# MainBoard.net
KiCad netlist of a schematic drawn in EAGLE
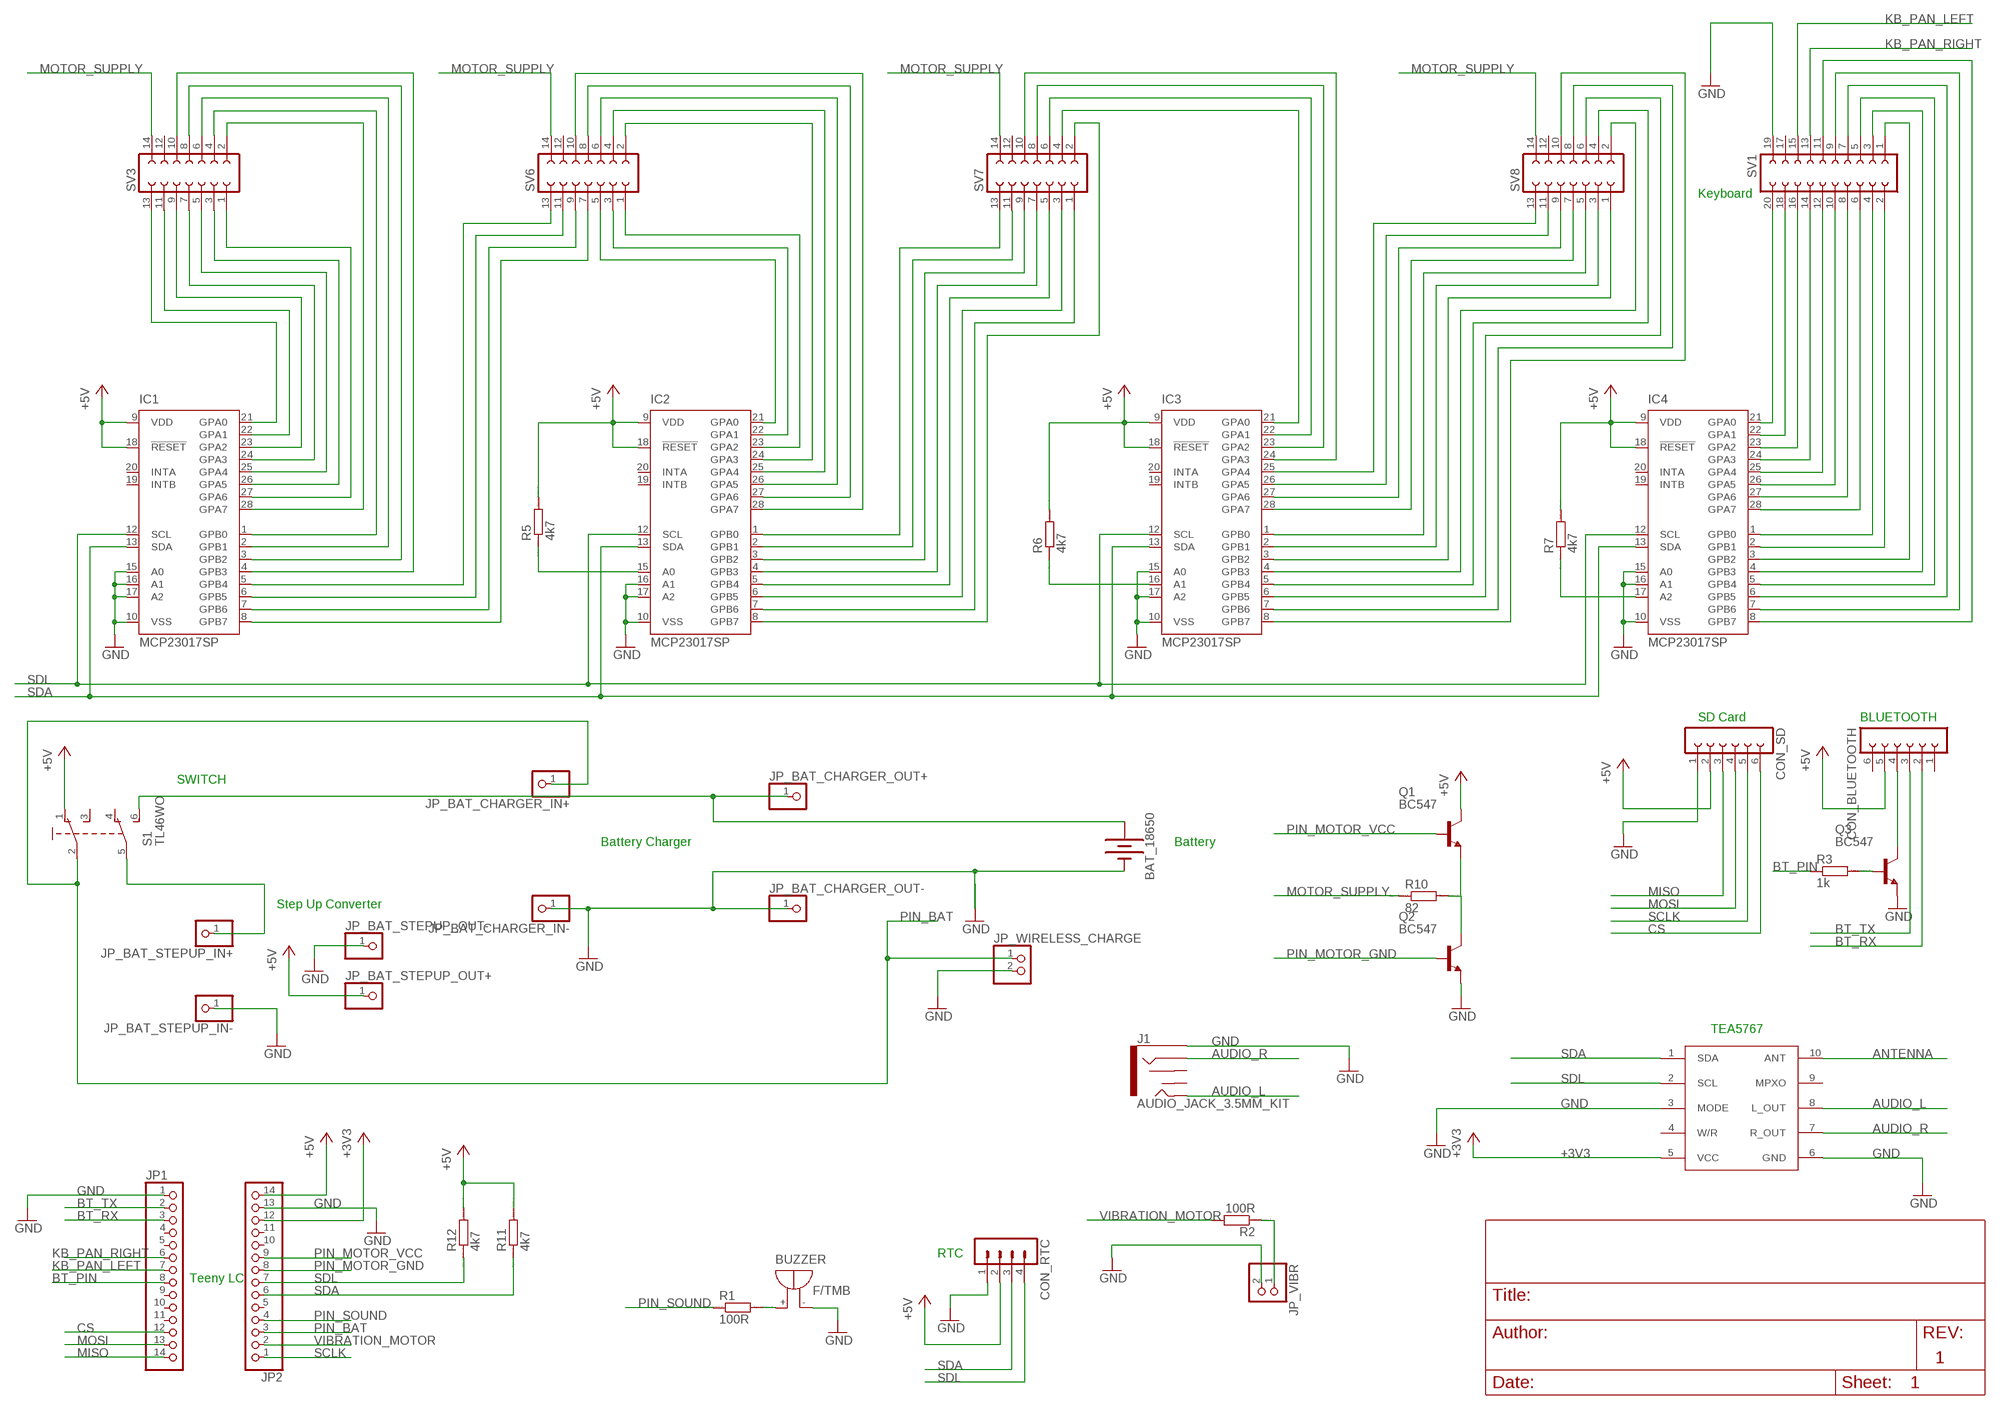
[diagram p0: schematic, sheet 1]

(export (version "E")
  (design (tool "Eeschema 10.0.6"))
  (components
    (comp (ref "BAT_18650")
      (value "BATTERY-18650")
      (footprint "eagle-import:BATTERY_18650-HOLDER")
      (libsource (lib "eagle-import") (part "BATTERY-18650"))
    )
    (comp (ref "BUZZER")
      (value "F/TMB")
      (footprint "eagle-import:F_TMB")
      (libsource (lib "eagle-import") (part "F/TMB"))
    )
    (comp (ref "CON_BLUETOOTH")
      (value "FE06-1")
      (footprint "eagle-import:FE06")
      (libsource (lib "eagle-import") (part "FE06-1"))
    )
    (comp (ref "CON_RTC")
      (value "MA04-1")
      (footprint "eagle-import:MA04-1")
      (libsource (lib "eagle-import") (part "MA04-1"))
    )
    (comp (ref "CON_SD")
      (value "FE06-1")
      (footprint "eagle-import:FE06")
      (libsource (lib "eagle-import") (part "FE06-1"))
    )
    (comp (ref "IC1")
      (value "MCP23017SP")
      (footprint "eagle-import:DIL28-3")
      (fields (field (name "MF") "MICROCHIP") (field (name "MPN") "MCP23017-E/SP"))
      (libsource (lib "eagle-import") (part "MCP23017SP"))
    )
    (comp (ref "IC2")
      (value "MCP23017SP")
      (footprint "eagle-import:DIL28-3")
      (fields (field (name "MF") "MICROCHIP") (field (name "MPN") "MCP23017-E/SP"))
      (libsource (lib "eagle-import") (part "MCP23017SP"))
    )
    (comp (ref "IC3")
      (value "MCP23017SP")
      (footprint "eagle-import:DIL28-3")
      (fields (field (name "MF") "MICROCHIP") (field (name "MPN") "MCP23017-E/SP"))
      (libsource (lib "eagle-import") (part "MCP23017SP"))
    )
    (comp (ref "IC4")
      (value "MCP23017SP")
      (footprint "eagle-import:DIL28-3")
      (fields (field (name "MF") "MICROCHIP") (field (name "MPN") "MCP23017-E/SP"))
      (libsource (lib "eagle-import") (part "MCP23017SP"))
    )
    (comp (ref "J1")
      (value "AUDIO_JACK_3.5MM_KIT")
      (footprint "eagle-import:AUDIO-JACK-KIT")
      (libsource (lib "eagle-import") (part "AUDIO_JACK_3.5MM_KIT"))
    )
    (comp (ref "JP1")
      (value "PINHD-1X14")
      (footprint "eagle-import:1X14")
      (libsource (lib "eagle-import") (part "PINHD-1X14"))
    )
    (comp (ref "JP2")
      (value "PINHD-1X14")
      (footprint "eagle-import:1X14")
      (libsource (lib "eagle-import") (part "PINHD-1X14"))
    )
    (comp (ref "JP_BAT_CHARGER_IN+")
      (value "PINHD-1X1")
      (footprint "eagle-import:1X01")
      (libsource (lib "eagle-import") (part "PINHD-1X1"))
    )
    (comp (ref "JP_BAT_CHARGER_IN-")
      (value "PINHD-1X1")
      (footprint "eagle-import:1X01")
      (libsource (lib "eagle-import") (part "PINHD-1X1"))
    )
    (comp (ref "JP_BAT_CHARGER_OUT+")
      (value "PINHD-1X1")
      (footprint "eagle-import:1X01")
      (libsource (lib "eagle-import") (part "PINHD-1X1"))
    )
    (comp (ref "JP_BAT_CHARGER_OUT-")
      (value "PINHD-1X1")
      (footprint "eagle-import:1X01")
      (libsource (lib "eagle-import") (part "PINHD-1X1"))
    )
    (comp (ref "JP_BAT_STEPUP_IN+")
      (value "PINHD-1X1")
      (footprint "eagle-import:1X01")
      (libsource (lib "eagle-import") (part "PINHD-1X1"))
    )
    (comp (ref "JP_BAT_STEPUP_IN-")
      (value "PINHD-1X1")
      (footprint "eagle-import:1X01")
      (libsource (lib "eagle-import") (part "PINHD-1X1"))
    )
    (comp (ref "JP_BAT_STEPUP_OUT+")
      (value "PINHD-1X1")
      (footprint "eagle-import:1X01")
      (libsource (lib "eagle-import") (part "PINHD-1X1"))
    )
    (comp (ref "JP_BAT_STEPUP_OUT-")
      (value "PINHD-1X1")
      (footprint "eagle-import:1X01")
      (libsource (lib "eagle-import") (part "PINHD-1X1"))
    )
    (comp (ref "JP_VIBR")
      (value "PINHD-1X2")
      (footprint "eagle-import:1X02")
      (libsource (lib "eagle-import") (part "PINHD-1X2"))
    )
    (comp (ref "JP_WIRELESS_CHARGE")
      (value "PINHD-1X2")
      (footprint "eagle-import:1X02")
      (libsource (lib "eagle-import") (part "PINHD-1X2"))
    )
    (comp (ref "Q1")
      (value "BC547")
      (footprint "eagle-import:TO92")
      (libsource (lib "eagle-import") (part "BC547"))
    )
    (comp (ref "Q2")
      (value "BC547")
      (footprint "eagle-import:TO92")
      (libsource (lib "eagle-import") (part "BC547"))
    )
    (comp (ref "Q3")
      (value "BC547")
      (footprint "eagle-import:TO92")
      (libsource (lib "eagle-import") (part "BC547"))
    )
    (comp (ref "R1")
      (value "100R")
      (footprint "eagle-import:R1206")
      (libsource (lib "eagle-import") (part "RR1206"))
    )
    (comp (ref "R2")
      (value "100R")
      (footprint "eagle-import:R1206")
      (libsource (lib "eagle-import") (part "RR1206"))
    )
    (comp (ref "R3")
      (value "1k")
      (footprint "eagle-import:R1206")
      (libsource (lib "eagle-import") (part "RR1206"))
    )
    (comp (ref "R5")
      (value "4k7")
      (footprint "eagle-import:R1206")
      (libsource (lib "eagle-import") (part "RR1206"))
    )
    (comp (ref "R6")
      (value "4k7")
      (footprint "eagle-import:R1206")
      (libsource (lib "eagle-import") (part "RR1206"))
    )
    (comp (ref "R7")
      (value "4k7")
      (footprint "eagle-import:R1206")
      (libsource (lib "eagle-import") (part "RR1206"))
    )
    (comp (ref "R10")
      (value "82")
      (footprint "eagle-import:R1206")
      (libsource (lib "eagle-import") (part "RR1206"))
    )
    (comp (ref "R11")
      (value "4k7")
      (footprint "eagle-import:R1206")
      (libsource (lib "eagle-import") (part "RR1206"))
    )
    (comp (ref "R12")
      (value "4k7")
      (footprint "eagle-import:R1206")
      (libsource (lib "eagle-import") (part "RR1206"))
    )
    (comp (ref "S1")
      (value "TL46WO")
      (footprint "eagle-import:TL4XWO")
      (libsource (lib "eagle-import") (part "TL46WO"))
    )
    (comp (ref "SV1")
      (value "FE10-2")
      (footprint "eagle-import:FE10-2")
      (libsource (lib "eagle-import") (part "FE10-2"))
    )
    (comp (ref "SV3")
      (value "FE07-2")
      (footprint "eagle-import:FE07-2")
      (libsource (lib "eagle-import") (part "FE07-2"))
    )
    (comp (ref "SV6")
      (value "FE07-2")
      (footprint "eagle-import:FE07-2")
      (libsource (lib "eagle-import") (part "FE07-2"))
    )
    (comp (ref "SV7")
      (value "FE07-2")
      (footprint "eagle-import:FE07-2")
      (libsource (lib "eagle-import") (part "FE07-2"))
    )
    (comp (ref "SV8")
      (value "FE07-2")
      (footprint "eagle-import:FE07-2")
      (libsource (lib "eagle-import") (part "FE07-2"))
    )
    (comp (ref "TEA5767")
      (value "TEA5767BREAKOUT")
      (footprint "eagle-import:TEA5767MM2")
      (libsource (lib "eagle-import") (part "TEA5767BREAKOUT"))
    )
  )
  (nets
    (net (code "1") (name "+3V3") (class "Default")
      (node (ref "JP2") (pin "12") (pinfunction "12_12") (pintype "passive"))
      (node (ref "TEA5767") (pin "5") (pinfunction "VCC_5") (pintype "bidirectional"))
    )
    (net (code "2") (name "+5V") (class "Default")
      (node (ref "CON_BLUETOOTH") (pin "5") (pinfunction "5_5") (pintype "passive"))
      (node (ref "CON_RTC") (pin "2") (pinfunction "2_2") (pintype "passive"))
      (node (ref "CON_SD") (pin "2") (pinfunction "2_2") (pintype "passive"))
      (node (ref "IC1") (pin "18") (pinfunction "~{RESET}_18") (pintype "input"))
      (node (ref "IC1") (pin "9") (pinfunction "VDD_9") (pintype "power_in"))
      (node (ref "IC2") (pin "18") (pinfunction "~{RESET}_18") (pintype "input"))
      (node (ref "IC2") (pin "9") (pinfunction "VDD_9") (pintype "power_in"))
      (node (ref "IC3") (pin "18") (pinfunction "~{RESET}_18") (pintype "input"))
      (node (ref "IC3") (pin "9") (pinfunction "VDD_9") (pintype "power_in"))
      (node (ref "IC4") (pin "18") (pinfunction "~{RESET}_18") (pintype "input"))
      (node (ref "IC4") (pin "9") (pinfunction "VDD_9") (pintype "power_in"))
      (node (ref "JP2") (pin "14") (pinfunction "14_14") (pintype "passive"))
      (node (ref "JP_BAT_STEPUP_OUT+") (pin "1") (pinfunction "1_1") (pintype "passive"))
      (node (ref "Q1") (pin "3") (pinfunction "C_3") (pintype "passive"))
      (node (ref "R11") (pin "2") (pinfunction "2_2") (pintype "passive"))
      (node (ref "R12") (pin "2") (pinfunction "2_2") (pintype "passive"))
      (node (ref "R5") (pin "2") (pinfunction "2_2") (pintype "passive"))
      (node (ref "R6") (pin "2") (pinfunction "2_2") (pintype "passive"))
      (node (ref "R7") (pin "2") (pinfunction "2_2") (pintype "passive"))
      (node (ref "S1") (pin "1") (pinfunction "O_1") (pintype "passive"))
    )
    (net (code "3") (name "/ANTENNA") (class "Default")
      (node (ref "TEA5767") (pin "10") (pinfunction "ANT_10") (pintype "bidirectional"))
    )
    (net (code "4") (name "/AUDIO_L") (class "Default")
      (node (ref "J1") (pin "TIP") (pinfunction "TIP_TIP") (pintype "bidirectional"))
      (node (ref "TEA5767") (pin "8") (pinfunction "L_OUT_8") (pintype "bidirectional"))
    )
    (net (code "5") (name "/AUDIO_R") (class "Default")
      (node (ref "J1") (pin "RING") (pinfunction "RING_RING") (pintype "bidirectional"))
      (node (ref "TEA5767") (pin "7") (pinfunction "R_OUT_7") (pintype "bidirectional"))
    )
    (net (code "6") (name "/BT_PIN") (class "Default")
      (node (ref "JP1") (pin "8") (pinfunction "8_8") (pintype "passive"))
      (node (ref "R3") (pin "1") (pinfunction "1_1") (pintype "passive"))
    )
    (net (code "7") (name "/BT_RX") (class "Default")
      (node (ref "CON_BLUETOOTH") (pin "2") (pinfunction "2_2") (pintype "passive"))
      (node (ref "JP1") (pin "3") (pinfunction "3_3") (pintype "passive"))
    )
    (net (code "8") (name "/BT_TX") (class "Default")
      (node (ref "CON_BLUETOOTH") (pin "3") (pinfunction "3_3") (pintype "passive"))
      (node (ref "JP1") (pin "2") (pinfunction "2_2") (pintype "passive"))
    )
    (net (code "9") (name "/CS") (class "Default")
      (node (ref "CON_SD") (pin "6") (pinfunction "6_6") (pintype "passive"))
      (node (ref "JP1") (pin "12") (pinfunction "12_12") (pintype "passive"))
    )
    (net (code "10") (name "/KB_PAN_LEFT") (class "Default")
      (node (ref "JP1") (pin "7") (pinfunction "7_7") (pintype "passive"))
      (node (ref "SV1") (pin "15") (pinfunction "15_15") (pintype "passive"))
    )
    (net (code "11") (name "/KB_PAN_RIGHT") (class "Default")
      (node (ref "JP1") (pin "6") (pinfunction "6_6") (pintype "passive"))
      (node (ref "SV1") (pin "13") (pinfunction "13_13") (pintype "passive"))
    )
    (net (code "12") (name "/MISO") (class "Default")
      (node (ref "CON_SD") (pin "3") (pinfunction "3_3") (pintype "passive"))
      (node (ref "JP1") (pin "14") (pinfunction "14_14") (pintype "passive"))
    )
    (net (code "13") (name "/MOSI") (class "Default")
      (node (ref "CON_SD") (pin "4") (pinfunction "4_4") (pintype "passive"))
      (node (ref "JP1") (pin "13") (pinfunction "13_13") (pintype "passive"))
    )
    (net (code "14") (name "/MOTOR_SUPPLY") (class "Default")
      (node (ref "R10") (pin "1") (pinfunction "1_1") (pintype "passive"))
      (node (ref "SV3") (pin "14") (pinfunction "14_14") (pintype "passive"))
      (node (ref "SV6") (pin "14") (pinfunction "14_14") (pintype "passive"))
      (node (ref "SV7") (pin "14") (pinfunction "14_14") (pintype "passive"))
      (node (ref "SV8") (pin "14") (pinfunction "14_14") (pintype "passive"))
    )
    (net (code "15") (name "/PIN_BAT") (class "Default")
      (node (ref "JP2") (pin "3") (pinfunction "3_3") (pintype "passive"))
      (node (ref "JP_BAT_CHARGER_IN+") (pin "1") (pinfunction "1_1") (pintype "passive"))
      (node (ref "JP_WIRELESS_CHARGE") (pin "1") (pinfunction "1_1") (pintype "passive"))
      (node (ref "S1") (pin "2") (pinfunction "P_2") (pintype "passive"))
    )
    (net (code "16") (name "/PIN_MOTOR_GND") (class "Default")
      (node (ref "JP2") (pin "8") (pinfunction "8_8") (pintype "passive"))
      (node (ref "Q2") (pin "2") (pinfunction "B_2") (pintype "passive"))
    )
    (net (code "17") (name "/PIN_MOTOR_VCC") (class "Default")
      (node (ref "JP2") (pin "9") (pinfunction "9_9") (pintype "passive"))
      (node (ref "Q1") (pin "2") (pinfunction "B_2") (pintype "passive"))
    )
    (net (code "18") (name "/PIN_SOUND") (class "Default")
      (node (ref "JP2") (pin "4") (pinfunction "4_4") (pintype "passive"))
      (node (ref "R1") (pin "1") (pinfunction "1_1") (pintype "passive"))
    )
    (net (code "19") (name "/SCLK") (class "Default")
      (node (ref "CON_SD") (pin "5") (pinfunction "5_5") (pintype "passive"))
      (node (ref "JP2") (pin "1") (pinfunction "1_1") (pintype "passive"))
    )
    (net (code "20") (name "/SDA") (class "Default")
      (node (ref "CON_RTC") (pin "3") (pinfunction "3_3") (pintype "passive"))
      (node (ref "IC1") (pin "13") (pinfunction "SDA_13") (pintype "bidirectional"))
      (node (ref "IC2") (pin "13") (pinfunction "SDA_13") (pintype "bidirectional"))
      (node (ref "IC3") (pin "13") (pinfunction "SDA_13") (pintype "bidirectional"))
      (node (ref "IC4") (pin "13") (pinfunction "SDA_13") (pintype "bidirectional"))
      (node (ref "JP2") (pin "6") (pinfunction "6_6") (pintype "passive"))
      (node (ref "R11") (pin "1") (pinfunction "1_1") (pintype "passive"))
      (node (ref "TEA5767") (pin "1") (pinfunction "SDA_1") (pintype "bidirectional"))
    )
    (net (code "21") (name "/SDL") (class "Default")
      (node (ref "CON_RTC") (pin "4") (pinfunction "4_4") (pintype "passive"))
      (node (ref "IC1") (pin "12") (pinfunction "SCL_12") (pintype "input"))
      (node (ref "IC2") (pin "12") (pinfunction "SCL_12") (pintype "input"))
      (node (ref "IC3") (pin "12") (pinfunction "SCL_12") (pintype "input"))
      (node (ref "IC4") (pin "12") (pinfunction "SCL_12") (pintype "input"))
      (node (ref "JP2") (pin "7") (pinfunction "7_7") (pintype "passive"))
      (node (ref "R12") (pin "1") (pinfunction "1_1") (pintype "passive"))
      (node (ref "TEA5767") (pin "2") (pinfunction "SCL_2") (pintype "bidirectional"))
    )
    (net (code "22") (name "/VIBRATION_MOTOR") (class "Default")
      (node (ref "JP2") (pin "2") (pinfunction "2_2") (pintype "passive"))
      (node (ref "R2") (pin "2") (pinfunction "2_2") (pintype "passive"))
    )
    (net (code "23") (name "GND") (class "Default")
      (node (ref "BAT_18650") (pin "GND@1") (pinfunction "-_GND@1") (pintype "power_in"))
      (node (ref "BUZZER") (pin "-") (pinfunction "-_-") (pintype "passive"))
      (node (ref "CON_RTC") (pin "1") (pinfunction "1_1") (pintype "passive"))
      (node (ref "CON_SD") (pin "1") (pinfunction "1_1") (pintype "passive"))
      (node (ref "IC1") (pin "10") (pinfunction "VSS_10") (pintype "power_in"))
      (node (ref "IC1") (pin "15") (pinfunction "A0_15") (pintype "input"))
      (node (ref "IC1") (pin "16") (pinfunction "A1_16") (pintype "input"))
      (node (ref "IC1") (pin "17") (pinfunction "A2_17") (pintype "input"))
      (node (ref "IC2") (pin "10") (pinfunction "VSS_10") (pintype "power_in"))
      (node (ref "IC2") (pin "16") (pinfunction "A1_16") (pintype "input"))
      (node (ref "IC2") (pin "17") (pinfunction "A2_17") (pintype "input"))
      (node (ref "IC3") (pin "10") (pinfunction "VSS_10") (pintype "power_in"))
      (node (ref "IC3") (pin "15") (pinfunction "A0_15") (pintype "input"))
      (node (ref "IC3") (pin "17") (pinfunction "A2_17") (pintype "input"))
      (node (ref "IC4") (pin "10") (pinfunction "VSS_10") (pintype "power_in"))
      (node (ref "IC4") (pin "15") (pinfunction "A0_15") (pintype "input"))
      (node (ref "IC4") (pin "16") (pinfunction "A1_16") (pintype "input"))
      (node (ref "J1") (pin "SLEEVE") (pinfunction "SLEEVE_SLEEVE") (pintype "bidirectional"))
      (node (ref "JP1") (pin "1") (pinfunction "1_1") (pintype "passive"))
      (node (ref "JP2") (pin "13") (pinfunction "13_13") (pintype "passive"))
      (node (ref "JP_BAT_CHARGER_IN-") (pin "1") (pinfunction "1_1") (pintype "passive"))
      (node (ref "JP_BAT_CHARGER_OUT-") (pin "1") (pinfunction "1_1") (pintype "passive"))
      (node (ref "JP_BAT_STEPUP_IN-") (pin "1") (pinfunction "1_1") (pintype "passive"))
      (node (ref "JP_BAT_STEPUP_OUT-") (pin "1") (pinfunction "1_1") (pintype "passive"))
      (node (ref "JP_VIBR") (pin "2") (pinfunction "2_2") (pintype "passive"))
      (node (ref "JP_WIRELESS_CHARGE") (pin "2") (pinfunction "2_2") (pintype "passive"))
      (node (ref "Q2") (pin "1") (pinfunction "E_1") (pintype "passive"))
      (node (ref "Q3") (pin "1") (pinfunction "E_1") (pintype "passive"))
      (node (ref "SV1") (pin "19") (pinfunction "19_19") (pintype "passive"))
      (node (ref "TEA5767") (pin "3") (pinfunction "MODE_3") (pintype "bidirectional"))
      (node (ref "TEA5767") (pin "6") (pinfunction "GND_6") (pintype "bidirectional"))
    )
    (net (code "24") (name "Net-(BAT_18650-+)") (class "Default")
      (node (ref "BAT_18650") (pin "PWR@1") (pinfunction "+_PWR@1") (pintype "power_in"))
      (node (ref "JP_BAT_CHARGER_OUT+") (pin "1") (pinfunction "1_1") (pintype "passive"))
      (node (ref "S1") (pin "6") (pinfunction "S1_6") (pintype "passive"))
    )
    (net (code "25") (name "Net-(BUZZER-Pad+)") (class "Default")
      (node (ref "BUZZER") (pin "+") (pinfunction "+_+") (pintype "passive"))
      (node (ref "R1") (pin "2") (pinfunction "2_2") (pintype "passive"))
    )
    (net (code "26") (name "Net-(IC1-GPA0)") (class "Default")
      (node (ref "IC1") (pin "21") (pinfunction "GPA0_21") (pintype "bidirectional"))
      (node (ref "SV3") (pin "13") (pinfunction "13_13") (pintype "passive"))
    )
    (net (code "27") (name "Net-(IC1-GPA1)") (class "Default")
      (node (ref "IC1") (pin "22") (pinfunction "GPA1_22") (pintype "bidirectional"))
      (node (ref "SV3") (pin "11") (pinfunction "11_11") (pintype "passive"))
    )
    (net (code "28") (name "Net-(IC1-GPA2)") (class "Default")
      (node (ref "IC1") (pin "23") (pinfunction "GPA2_23") (pintype "bidirectional"))
      (node (ref "SV3") (pin "9") (pinfunction "9_9") (pintype "passive"))
    )
    (net (code "29") (name "Net-(IC1-GPA3)") (class "Default")
      (node (ref "IC1") (pin "24") (pinfunction "GPA3_24") (pintype "bidirectional"))
      (node (ref "SV3") (pin "7") (pinfunction "7_7") (pintype "passive"))
    )
    (net (code "30") (name "Net-(IC1-GPA4)") (class "Default")
      (node (ref "IC1") (pin "25") (pinfunction "GPA4_25") (pintype "bidirectional"))
      (node (ref "SV3") (pin "5") (pinfunction "5_5") (pintype "passive"))
    )
    (net (code "31") (name "Net-(IC1-GPA5)") (class "Default")
      (node (ref "IC1") (pin "26") (pinfunction "GPA5_26") (pintype "bidirectional"))
      (node (ref "SV3") (pin "3") (pinfunction "3_3") (pintype "passive"))
    )
    (net (code "32") (name "Net-(IC1-GPA6)") (class "Default")
      (node (ref "IC1") (pin "27") (pinfunction "GPA6_27") (pintype "bidirectional"))
      (node (ref "SV3") (pin "1") (pinfunction "1_1") (pintype "passive"))
    )
    (net (code "33") (name "Net-(IC1-GPA7)") (class "Default")
      (node (ref "IC1") (pin "28") (pinfunction "GPA7_28") (pintype "bidirectional"))
      (node (ref "SV3") (pin "2") (pinfunction "2_2") (pintype "passive"))
    )
    (net (code "34") (name "Net-(IC1-GPB0)") (class "Default")
      (node (ref "IC1") (pin "1") (pinfunction "GPB0_1") (pintype "bidirectional"))
      (node (ref "SV3") (pin "4") (pinfunction "4_4") (pintype "passive"))
    )
    (net (code "35") (name "Net-(IC1-GPB1)") (class "Default")
      (node (ref "IC1") (pin "2") (pinfunction "GPB1_2") (pintype "bidirectional"))
      (node (ref "SV3") (pin "6") (pinfunction "6_6") (pintype "passive"))
    )
    (net (code "36") (name "Net-(IC1-GPB2)") (class "Default")
      (node (ref "IC1") (pin "3") (pinfunction "GPB2_3") (pintype "bidirectional"))
      (node (ref "SV3") (pin "8") (pinfunction "8_8") (pintype "passive"))
    )
    (net (code "37") (name "Net-(IC1-GPB3)") (class "Default")
      (node (ref "IC1") (pin "4") (pinfunction "GPB3_4") (pintype "bidirectional"))
      (node (ref "SV3") (pin "10") (pinfunction "10_10") (pintype "passive"))
    )
    (net (code "38") (name "Net-(IC1-GPB4)") (class "Default")
      (node (ref "IC1") (pin "5") (pinfunction "GPB4_5") (pintype "bidirectional"))
      (node (ref "SV6") (pin "13") (pinfunction "13_13") (pintype "passive"))
    )
    (net (code "39") (name "Net-(IC1-GPB5)") (class "Default")
      (node (ref "IC1") (pin "6") (pinfunction "GPB5_6") (pintype "bidirectional"))
      (node (ref "SV6") (pin "11") (pinfunction "11_11") (pintype "passive"))
    )
    (net (code "40") (name "Net-(IC1-GPB6)") (class "Default")
      (node (ref "IC1") (pin "7") (pinfunction "GPB6_7") (pintype "bidirectional"))
      (node (ref "SV6") (pin "9") (pinfunction "9_9") (pintype "passive"))
    )
    (net (code "41") (name "Net-(IC1-GPB7)") (class "Default")
      (node (ref "IC1") (pin "8") (pinfunction "GPB7_8") (pintype "bidirectional"))
      (node (ref "SV6") (pin "7") (pinfunction "7_7") (pintype "passive"))
    )
    (net (code "42") (name "Net-(IC2-A0)") (class "Default")
      (node (ref "IC2") (pin "15") (pinfunction "A0_15") (pintype "input"))
      (node (ref "R5") (pin "1") (pinfunction "1_1") (pintype "passive"))
    )
    (net (code "43") (name "Net-(IC2-GPA0)") (class "Default")
      (node (ref "IC2") (pin "21") (pinfunction "GPA0_21") (pintype "bidirectional"))
      (node (ref "SV6") (pin "5") (pinfunction "5_5") (pintype "passive"))
    )
    (net (code "44") (name "Net-(IC2-GPA1)") (class "Default")
      (node (ref "IC2") (pin "22") (pinfunction "GPA1_22") (pintype "bidirectional"))
      (node (ref "SV6") (pin "3") (pinfunction "3_3") (pintype "passive"))
    )
    (net (code "45") (name "Net-(IC2-GPA2)") (class "Default")
      (node (ref "IC2") (pin "23") (pinfunction "GPA2_23") (pintype "bidirectional"))
      (node (ref "SV6") (pin "1") (pinfunction "1_1") (pintype "passive"))
    )
    (net (code "46") (name "Net-(IC2-GPA3)") (class "Default")
      (node (ref "IC2") (pin "24") (pinfunction "GPA3_24") (pintype "bidirectional"))
      (node (ref "SV6") (pin "2") (pinfunction "2_2") (pintype "passive"))
    )
    (net (code "47") (name "Net-(IC2-GPA4)") (class "Default")
      (node (ref "IC2") (pin "25") (pinfunction "GPA4_25") (pintype "bidirectional"))
      (node (ref "SV6") (pin "4") (pinfunction "4_4") (pintype "passive"))
    )
    (net (code "48") (name "Net-(IC2-GPA5)") (class "Default")
      (node (ref "IC2") (pin "26") (pinfunction "GPA5_26") (pintype "bidirectional"))
      (node (ref "SV6") (pin "6") (pinfunction "6_6") (pintype "passive"))
    )
    (net (code "49") (name "Net-(IC2-GPA6)") (class "Default")
      (node (ref "IC2") (pin "27") (pinfunction "GPA6_27") (pintype "bidirectional"))
      (node (ref "SV6") (pin "8") (pinfunction "8_8") (pintype "passive"))
    )
    (net (code "50") (name "Net-(IC2-GPA7)") (class "Default")
      (node (ref "IC2") (pin "28") (pinfunction "GPA7_28") (pintype "bidirectional"))
      (node (ref "SV6") (pin "10") (pinfunction "10_10") (pintype "passive"))
    )
    (net (code "51") (name "Net-(IC2-GPB0)") (class "Default")
      (node (ref "IC2") (pin "1") (pinfunction "GPB0_1") (pintype "bidirectional"))
      (node (ref "SV7") (pin "13") (pinfunction "13_13") (pintype "passive"))
    )
    (net (code "52") (name "Net-(IC2-GPB1)") (class "Default")
      (node (ref "IC2") (pin "2") (pinfunction "GPB1_2") (pintype "bidirectional"))
      (node (ref "SV7") (pin "11") (pinfunction "11_11") (pintype "passive"))
    )
    (net (code "53") (name "Net-(IC2-GPB2)") (class "Default")
      (node (ref "IC2") (pin "3") (pinfunction "GPB2_3") (pintype "bidirectional"))
      (node (ref "SV7") (pin "9") (pinfunction "9_9") (pintype "passive"))
    )
    (net (code "54") (name "Net-(IC2-GPB3)") (class "Default")
      (node (ref "IC2") (pin "4") (pinfunction "GPB3_4") (pintype "bidirectional"))
      (node (ref "SV7") (pin "7") (pinfunction "7_7") (pintype "passive"))
    )
    (net (code "55") (name "Net-(IC2-GPB4)") (class "Default")
      (node (ref "IC2") (pin "5") (pinfunction "GPB4_5") (pintype "bidirectional"))
      (node (ref "SV7") (pin "5") (pinfunction "5_5") (pintype "passive"))
    )
    (net (code "56") (name "Net-(IC2-GPB5)") (class "Default")
      (node (ref "IC2") (pin "6") (pinfunction "GPB5_6") (pintype "bidirectional"))
      (node (ref "SV7") (pin "3") (pinfunction "3_3") (pintype "passive"))
    )
    (net (code "57") (name "Net-(IC2-GPB6)") (class "Default")
      (node (ref "IC2") (pin "7") (pinfunction "GPB6_7") (pintype "bidirectional"))
      (node (ref "SV7") (pin "1") (pinfunction "1_1") (pintype "passive"))
    )
    (net (code "58") (name "Net-(IC2-GPB7)") (class "Default")
      (node (ref "IC2") (pin "8") (pinfunction "GPB7_8") (pintype "bidirectional"))
      (node (ref "SV7") (pin "2") (pinfunction "2_2") (pintype "passive"))
    )
    (net (code "59") (name "Net-(IC3-A1)") (class "Default")
      (node (ref "IC3") (pin "16") (pinfunction "A1_16") (pintype "input"))
      (node (ref "R6") (pin "1") (pinfunction "1_1") (pintype "passive"))
    )
    (net (code "60") (name "Net-(IC3-GPA0)") (class "Default")
      (node (ref "IC3") (pin "21") (pinfunction "GPA0_21") (pintype "bidirectional"))
      (node (ref "SV7") (pin "4") (pinfunction "4_4") (pintype "passive"))
    )
    (net (code "61") (name "Net-(IC3-GPA1)") (class "Default")
      (node (ref "IC3") (pin "22") (pinfunction "GPA1_22") (pintype "bidirectional"))
      (node (ref "SV7") (pin "6") (pinfunction "6_6") (pintype "passive"))
    )
    (net (code "62") (name "Net-(IC3-GPA2)") (class "Default")
      (node (ref "IC3") (pin "23") (pinfunction "GPA2_23") (pintype "bidirectional"))
      (node (ref "SV7") (pin "8") (pinfunction "8_8") (pintype "passive"))
    )
    (net (code "63") (name "Net-(IC3-GPA3)") (class "Default")
      (node (ref "IC3") (pin "24") (pinfunction "GPA3_24") (pintype "bidirectional"))
      (node (ref "SV7") (pin "10") (pinfunction "10_10") (pintype "passive"))
    )
    (net (code "64") (name "Net-(IC3-GPA4)") (class "Default")
      (node (ref "IC3") (pin "25") (pinfunction "GPA4_25") (pintype "bidirectional"))
      (node (ref "SV8") (pin "13") (pinfunction "13_13") (pintype "passive"))
    )
    (net (code "65") (name "Net-(IC3-GPA5)") (class "Default")
      (node (ref "IC3") (pin "26") (pinfunction "GPA5_26") (pintype "bidirectional"))
      (node (ref "SV8") (pin "11") (pinfunction "11_11") (pintype "passive"))
    )
    (net (code "66") (name "Net-(IC3-GPA6)") (class "Default")
      (node (ref "IC3") (pin "27") (pinfunction "GPA6_27") (pintype "bidirectional"))
      (node (ref "SV8") (pin "9") (pinfunction "9_9") (pintype "passive"))
    )
    (net (code "67") (name "Net-(IC3-GPA7)") (class "Default")
      (node (ref "IC3") (pin "28") (pinfunction "GPA7_28") (pintype "bidirectional"))
      (node (ref "SV8") (pin "7") (pinfunction "7_7") (pintype "passive"))
    )
    (net (code "68") (name "Net-(IC3-GPB0)") (class "Default")
      (node (ref "IC3") (pin "1") (pinfunction "GPB0_1") (pintype "bidirectional"))
      (node (ref "SV8") (pin "5") (pinfunction "5_5") (pintype "passive"))
    )
    (net (code "69") (name "Net-(IC3-GPB1)") (class "Default")
      (node (ref "IC3") (pin "2") (pinfunction "GPB1_2") (pintype "bidirectional"))
      (node (ref "SV8") (pin "3") (pinfunction "3_3") (pintype "passive"))
    )
    (net (code "70") (name "Net-(IC3-GPB2)") (class "Default")
      (node (ref "IC3") (pin "3") (pinfunction "GPB2_3") (pintype "bidirectional"))
      (node (ref "SV8") (pin "1") (pinfunction "1_1") (pintype "passive"))
    )
    (net (code "71") (name "Net-(IC3-GPB3)") (class "Default")
      (node (ref "IC3") (pin "4") (pinfunction "GPB3_4") (pintype "bidirectional"))
      (node (ref "SV8") (pin "2") (pinfunction "2_2") (pintype "passive"))
    )
    (net (code "72") (name "Net-(IC3-GPB4)") (class "Default")
      (node (ref "IC3") (pin "5") (pinfunction "GPB4_5") (pintype "bidirectional"))
      (node (ref "SV8") (pin "4") (pinfunction "4_4") (pintype "passive"))
    )
    (net (code "73") (name "Net-(IC3-GPB5)") (class "Default")
      (node (ref "IC3") (pin "6") (pinfunction "GPB5_6") (pintype "bidirectional"))
      (node (ref "SV8") (pin "6") (pinfunction "6_6") (pintype "passive"))
    )
    (net (code "74") (name "Net-(IC3-GPB6)") (class "Default")
      (node (ref "IC3") (pin "7") (pinfunction "GPB6_7") (pintype "bidirectional"))
      (node (ref "SV8") (pin "8") (pinfunction "8_8") (pintype "passive"))
    )
    (net (code "75") (name "Net-(IC3-GPB7)") (class "Default")
      (node (ref "IC3") (pin "8") (pinfunction "GPB7_8") (pintype "bidirectional"))
      (node (ref "SV8") (pin "10") (pinfunction "10_10") (pintype "passive"))
    )
    (net (code "76") (name "Net-(IC4-A2)") (class "Default")
      (node (ref "IC4") (pin "17") (pinfunction "A2_17") (pintype "input"))
      (node (ref "R7") (pin "1") (pinfunction "1_1") (pintype "passive"))
    )
    (net (code "77") (name "Net-(IC4-GPA0)") (class "Default")
      (node (ref "IC4") (pin "21") (pinfunction "GPA0_21") (pintype "bidirectional"))
      (node (ref "SV1") (pin "20") (pinfunction "20_20") (pintype "passive"))
    )
    (net (code "78") (name "Net-(IC4-GPA1)") (class "Default")
      (node (ref "IC4") (pin "22") (pinfunction "GPA1_22") (pintype "bidirectional"))
      (node (ref "SV1") (pin "18") (pinfunction "18_18") (pintype "passive"))
    )
    (net (code "79") (name "Net-(IC4-GPA2)") (class "Default")
      (node (ref "IC4") (pin "23") (pinfunction "GPA2_23") (pintype "bidirectional"))
      (node (ref "SV1") (pin "16") (pinfunction "16_16") (pintype "passive"))
    )
    (net (code "80") (name "Net-(IC4-GPA3)") (class "Default")
      (node (ref "IC4") (pin "24") (pinfunction "GPA3_24") (pintype "bidirectional"))
      (node (ref "SV1") (pin "14") (pinfunction "14_14") (pintype "passive"))
    )
    (net (code "81") (name "Net-(IC4-GPA4)") (class "Default")
      (node (ref "IC4") (pin "25") (pinfunction "GPA4_25") (pintype "bidirectional"))
      (node (ref "SV1") (pin "12") (pinfunction "12_12") (pintype "passive"))
    )
    (net (code "82") (name "Net-(IC4-GPA5)") (class "Default")
      (node (ref "IC4") (pin "26") (pinfunction "GPA5_26") (pintype "bidirectional"))
      (node (ref "SV1") (pin "10") (pinfunction "10_10") (pintype "passive"))
    )
    (net (code "83") (name "Net-(IC4-GPA6)") (class "Default")
      (node (ref "IC4") (pin "27") (pinfunction "GPA6_27") (pintype "bidirectional"))
      (node (ref "SV1") (pin "8") (pinfunction "8_8") (pintype "passive"))
    )
    (net (code "84") (name "Net-(IC4-GPA7)") (class "Default")
      (node (ref "IC4") (pin "28") (pinfunction "GPA7_28") (pintype "bidirectional"))
      (node (ref "SV1") (pin "6") (pinfunction "6_6") (pintype "passive"))
    )
    (net (code "85") (name "Net-(IC4-GPB0)") (class "Default")
      (node (ref "IC4") (pin "1") (pinfunction "GPB0_1") (pintype "bidirectional"))
      (node (ref "SV1") (pin "4") (pinfunction "4_4") (pintype "passive"))
    )
    (net (code "86") (name "Net-(IC4-GPB1)") (class "Default")
      (node (ref "IC4") (pin "2") (pinfunction "GPB1_2") (pintype "bidirectional"))
      (node (ref "SV1") (pin "2") (pinfunction "2_2") (pintype "passive"))
    )
    (net (code "87") (name "Net-(IC4-GPB2)") (class "Default")
      (node (ref "IC4") (pin "3") (pinfunction "GPB2_3") (pintype "bidirectional"))
      (node (ref "SV1") (pin "1") (pinfunction "1_1") (pintype "passive"))
    )
    (net (code "88") (name "Net-(IC4-GPB3)") (class "Default")
      (node (ref "IC4") (pin "4") (pinfunction "GPB3_4") (pintype "bidirectional"))
      (node (ref "SV1") (pin "3") (pinfunction "3_3") (pintype "passive"))
    )
    (net (code "89") (name "Net-(IC4-GPB4)") (class "Default")
      (node (ref "IC4") (pin "5") (pinfunction "GPB4_5") (pintype "bidirectional"))
      (node (ref "SV1") (pin "5") (pinfunction "5_5") (pintype "passive"))
    )
    (net (code "90") (name "Net-(IC4-GPB5)") (class "Default")
      (node (ref "IC4") (pin "6") (pinfunction "GPB5_6") (pintype "bidirectional"))
      (node (ref "SV1") (pin "7") (pinfunction "7_7") (pintype "passive"))
    )
    (net (code "91") (name "Net-(IC4-GPB6)") (class "Default")
      (node (ref "IC4") (pin "7") (pinfunction "GPB6_7") (pintype "bidirectional"))
      (node (ref "SV1") (pin "9") (pinfunction "9_9") (pintype "passive"))
    )
    (net (code "92") (name "Net-(IC4-GPB7)") (class "Default")
      (node (ref "IC4") (pin "8") (pinfunction "GPB7_8") (pintype "bidirectional"))
      (node (ref "SV1") (pin "11") (pinfunction "11_11") (pintype "passive"))
    )
    (net (code "93") (name "Net-(JP_VIBR-Pad1)") (class "Default")
      (node (ref "JP_VIBR") (pin "1") (pinfunction "1_1") (pintype "passive"))
      (node (ref "R2") (pin "1") (pinfunction "1_1") (pintype "passive"))
    )
    (net (code "94") (name "Net-(Q1-E)") (class "Default")
      (node (ref "Q1") (pin "1") (pinfunction "E_1") (pintype "passive"))
      (node (ref "Q2") (pin "3") (pinfunction "C_3") (pintype "passive"))
      (node (ref "R10") (pin "2") (pinfunction "2_2") (pintype "passive"))
    )
    (net (code "95") (name "Net-(Q3-B)") (class "Default")
      (node (ref "Q3") (pin "2") (pinfunction "B_2") (pintype "passive"))
      (node (ref "R3") (pin "2") (pinfunction "2_2") (pintype "passive"))
    )
    (net (code "96") (name "Net-(Q3-C)") (class "Default")
      (node (ref "CON_BLUETOOTH") (pin "4") (pinfunction "4_4") (pintype "passive"))
      (node (ref "Q3") (pin "3") (pinfunction "C_3") (pintype "passive"))
    )
    (net (code "97") (name "Net-(S1-P1)") (class "Default")
      (node (ref "JP_BAT_STEPUP_IN+") (pin "1") (pinfunction "1_1") (pintype "passive"))
      (node (ref "S1") (pin "5") (pinfunction "P1_5") (pintype "passive"))
    )
    (net (code "98") (name "unconnected-(CON_BLUETOOTH-Pad1)") (class "Default")
      (node (ref "CON_BLUETOOTH") (pin "1") (pinfunction "1_1") (pintype "passive"))
    )
    (net (code "99") (name "unconnected-(CON_BLUETOOTH-Pad6)") (class "Default")
      (node (ref "CON_BLUETOOTH") (pin "6") (pinfunction "6_6") (pintype "passive"))
    )
    (net (code "100") (name "unconnected-(IC1-INTA-Pad20)") (class "Default")
      (node (ref "IC1") (pin "20") (pinfunction "INTA_20") (pintype "output"))
    )
    (net (code "101") (name "unconnected-(IC1-INTB-Pad19)") (class "Default")
      (node (ref "IC1") (pin "19") (pinfunction "INTB_19") (pintype "output"))
    )
    (net (code "102") (name "unconnected-(IC2-INTA-Pad20)") (class "Default")
      (node (ref "IC2") (pin "20") (pinfunction "INTA_20") (pintype "output"))
    )
    (net (code "103") (name "unconnected-(IC2-INTB-Pad19)") (class "Default")
      (node (ref "IC2") (pin "19") (pinfunction "INTB_19") (pintype "output"))
    )
    (net (code "104") (name "unconnected-(IC3-INTA-Pad20)") (class "Default")
      (node (ref "IC3") (pin "20") (pinfunction "INTA_20") (pintype "output"))
    )
    (net (code "105") (name "unconnected-(IC3-INTB-Pad19)") (class "Default")
      (node (ref "IC3") (pin "19") (pinfunction "INTB_19") (pintype "output"))
    )
    (net (code "106") (name "unconnected-(IC4-INTA-Pad20)") (class "Default")
      (node (ref "IC4") (pin "20") (pinfunction "INTA_20") (pintype "output"))
    )
    (net (code "107") (name "unconnected-(IC4-INTB-Pad19)") (class "Default")
      (node (ref "IC4") (pin "19") (pinfunction "INTB_19") (pintype "output"))
    )
    (net (code "108") (name "unconnected-(J1-PadRSH)") (class "Default")
      (node (ref "J1") (pin "RSH") (pinfunction "RSH_RSH") (pintype "bidirectional"))
    )
    (net (code "109") (name "unconnected-(J1-PadTSH)") (class "Default")
      (node (ref "J1") (pin "TSH") (pinfunction "TSH_TSH") (pintype "bidirectional"))
    )
    (net (code "110") (name "unconnected-(JP1-Pad4)") (class "Default")
      (node (ref "JP1") (pin "4") (pinfunction "4_4") (pintype "passive"))
    )
    (net (code "111") (name "unconnected-(JP1-Pad5)") (class "Default")
      (node (ref "JP1") (pin "5") (pinfunction "5_5") (pintype "passive"))
    )
    (net (code "112") (name "unconnected-(JP1-Pad9)") (class "Default")
      (node (ref "JP1") (pin "9") (pinfunction "9_9") (pintype "passive"))
    )
    (net (code "113") (name "unconnected-(JP1-Pad10)") (class "Default")
      (node (ref "JP1") (pin "10") (pinfunction "10_10") (pintype "passive"))
    )
    (net (code "114") (name "unconnected-(JP1-Pad11)") (class "Default")
      (node (ref "JP1") (pin "11") (pinfunction "11_11") (pintype "passive"))
    )
    (net (code "115") (name "unconnected-(JP2-Pad5)") (class "Default")
      (node (ref "JP2") (pin "5") (pinfunction "5_5") (pintype "passive"))
    )
    (net (code "116") (name "unconnected-(JP2-Pad10)") (class "Default")
      (node (ref "JP2") (pin "10") (pinfunction "10_10") (pintype "passive"))
    )
    (net (code "117") (name "unconnected-(JP2-Pad11)") (class "Default")
      (node (ref "JP2") (pin "11") (pinfunction "11_11") (pintype "passive"))
    )
    (net (code "118") (name "unconnected-(S1-O1-Pad4)") (class "Default")
      (node (ref "S1") (pin "4") (pinfunction "O1_4") (pintype "passive"))
    )
    (net (code "119") (name "unconnected-(S1-S-Pad3)") (class "Default")
      (node (ref "S1") (pin "3") (pinfunction "S_3") (pintype "passive"))
    )
    (net (code "120") (name "unconnected-(SV1-Pad17)") (class "Default")
      (node (ref "SV1") (pin "17") (pinfunction "17_17") (pintype "passive"))
    )
    (net (code "121") (name "unconnected-(SV3-Pad12)") (class "Default")
      (node (ref "SV3") (pin "12") (pinfunction "12_12") (pintype "passive"))
    )
    (net (code "122") (name "unconnected-(SV6-Pad12)") (class "Default")
      (node (ref "SV6") (pin "12") (pinfunction "12_12") (pintype "passive"))
    )
    (net (code "123") (name "unconnected-(SV7-Pad12)") (class "Default")
      (node (ref "SV7") (pin "12") (pinfunction "12_12") (pintype "passive"))
    )
    (net (code "124") (name "unconnected-(SV8-Pad12)") (class "Default")
      (node (ref "SV8") (pin "12") (pinfunction "12_12") (pintype "passive"))
    )
    (net (code "125") (name "unconnected-(TEA5767-MPXO-Pad9)") (class "Default")
      (node (ref "TEA5767") (pin "9") (pinfunction "MPXO_9") (pintype "bidirectional"))
    )
    (net (code "126") (name "unconnected-(TEA5767-W{slash}R-Pad4)") (class "Default")
      (node (ref "TEA5767") (pin "4") (pinfunction "W/R_4") (pintype "bidirectional"))
    )
  )
)
